# WAirU_v1_1.net
KiCad netlist of a schematic drawn in EAGLE
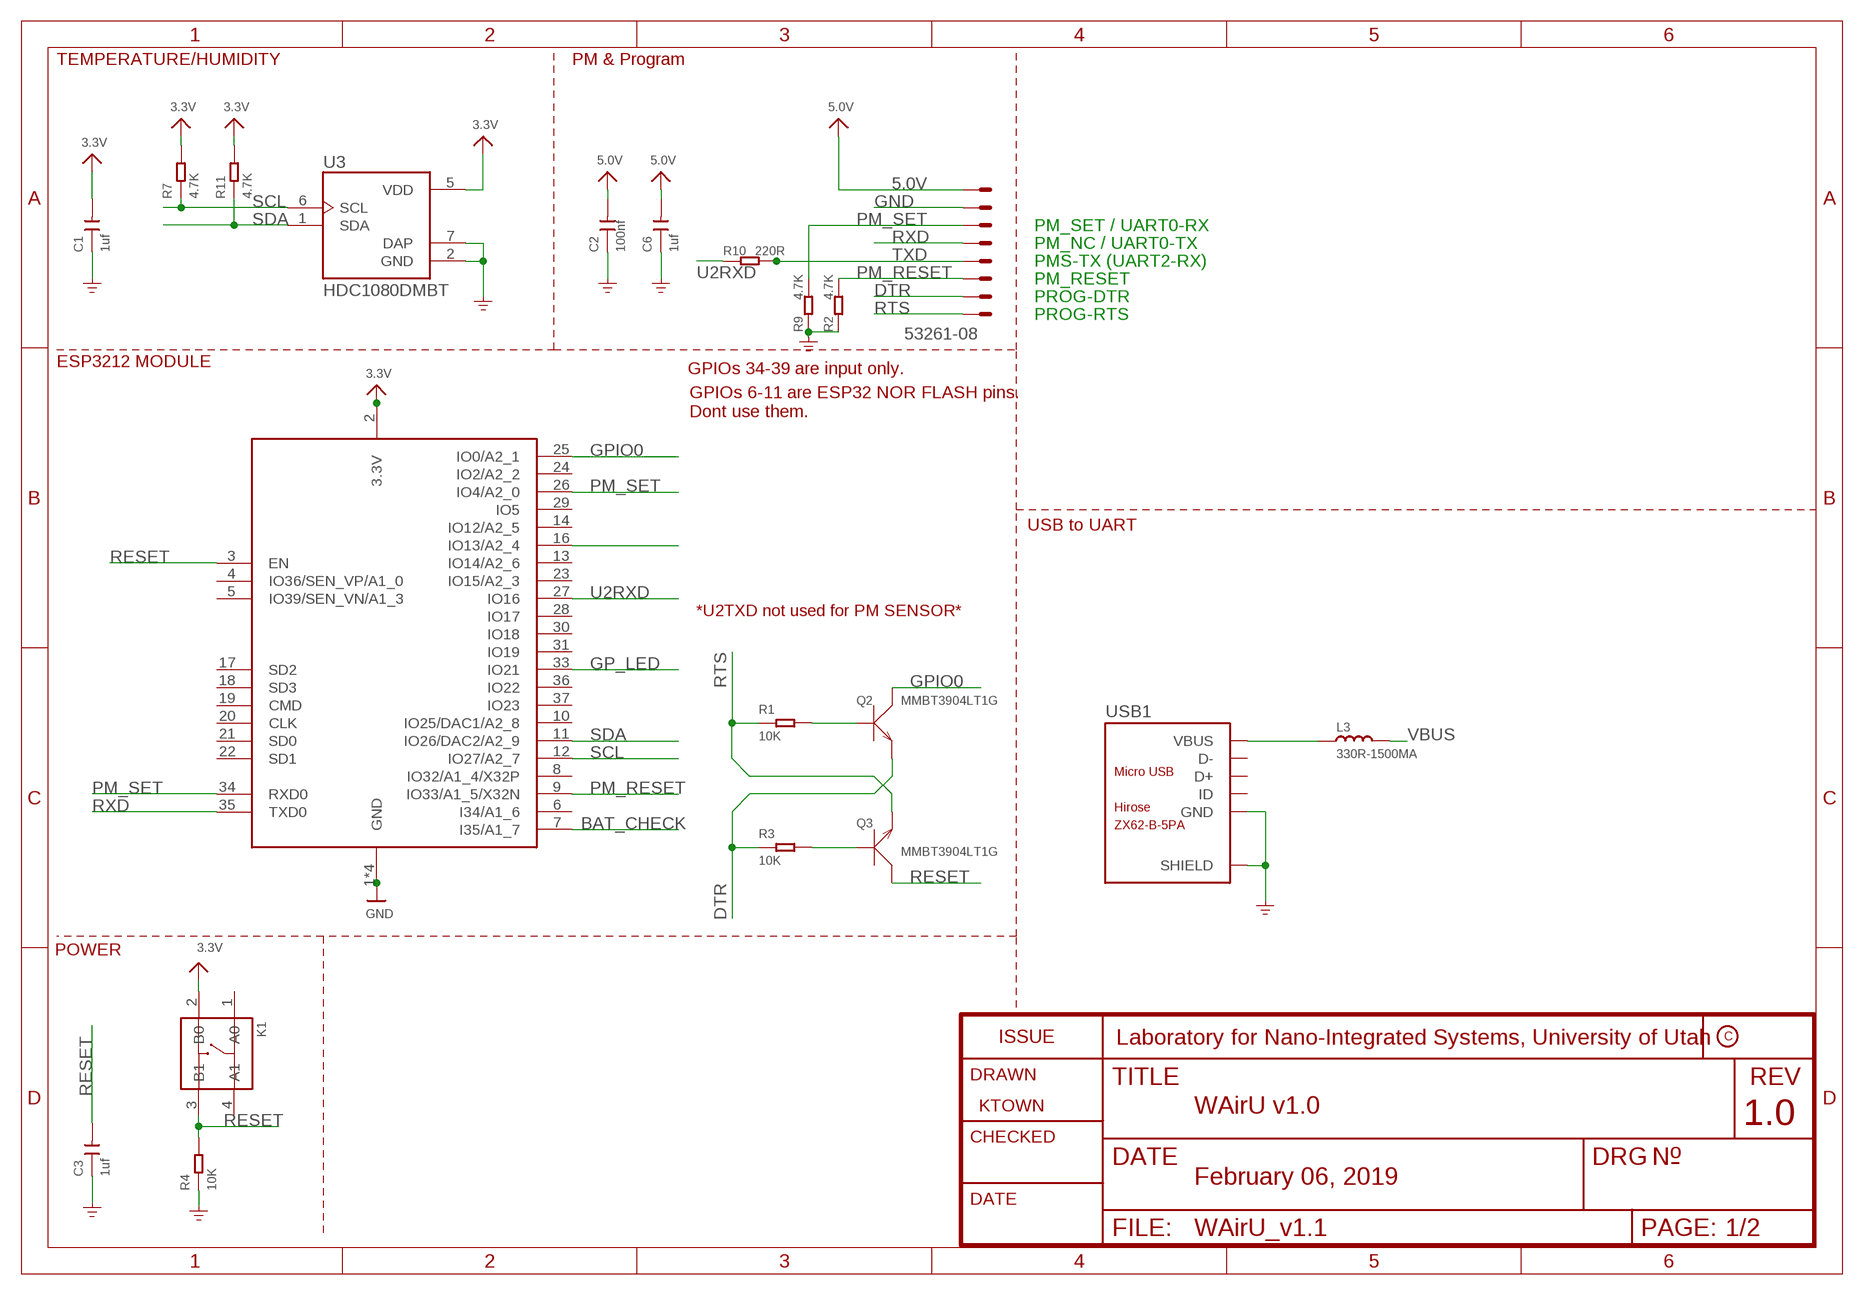
[diagram p0: schematic, sheet 1]
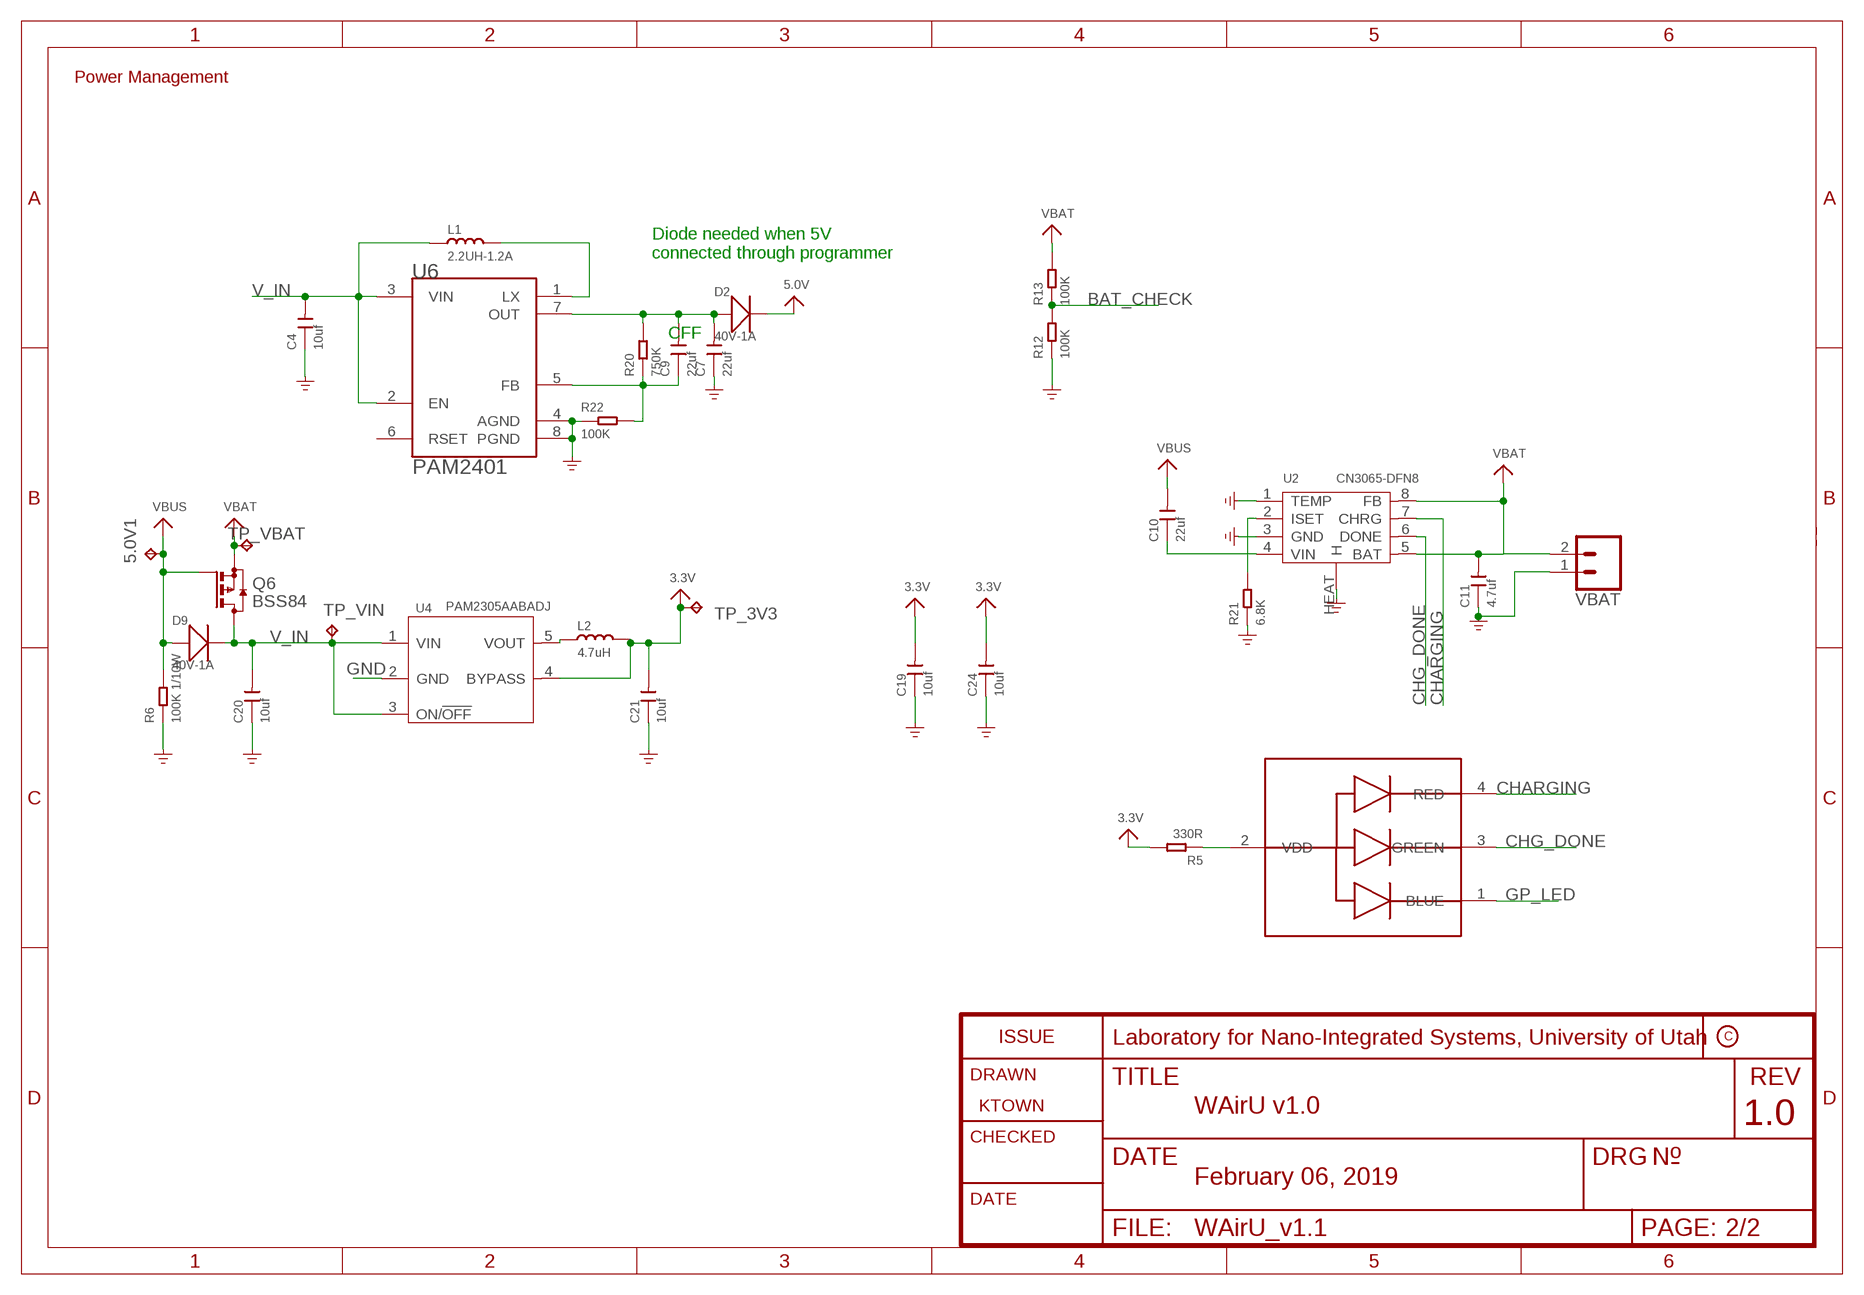
[diagram p1: schematic, sheet 2]

(export (version "E")
  (design (tool "Eeschema 10.0.6"))
  (components
    (comp (ref "5.0V1")
      (value "TPTP20SQ")
      (footprint "eagle-import:TP20SQ")
      (libsource (lib "eagle-import") (part "TPTP20SQ"))
    )
    (comp (ref "C4")
      (value "10uf")
      (footprint "eagle-import:C0603")
      (fields (field (name "MPN") "CC0603KRX5R6BB106"))
      (libsource (lib "eagle-import") (part "Seeed-Capacitor_CERAMIC-10UF-10V-10%-X5R(0603)"))
    )
    (comp (ref "C7")
      (value "22uf")
      (footprint "eagle-import:C0603")
      (fields (field (name "MPN") "CC0603KRX5R6BB106"))
      (libsource (lib "eagle-import") (part "CERAMIC-10UF-10V-10%-X5R(0603)"))
    )
    (comp (ref "C9")
      (value "22uf")
      (footprint "eagle-import:C0603")
      (fields (field (name "MPN") "CC0603KRX5R6BB106"))
      (libsource (lib "eagle-import") (part "CERAMIC-10UF-10V-10%-X5R(0603)"))
    )
    (comp (ref "C10")
      (value "22uf")
      (footprint "eagle-import:C0603")
      (fields (field (name "MPN") "CC0603KRX5R6BB106"))
      (libsource (lib "eagle-import") (part "CERAMIC-10UF-10V-10%-X5R(0603)"))
    )
    (comp (ref "C11")
      (value "4.7uf")
      (footprint "eagle-import:C0603")
      (fields (field (name "MPN") "CC0603KRX5R6BB475"))
      (libsource (lib "eagle-import") (part "CERAMIC-4.7UF-10V-10%-X5R(0603)"))
    )
    (comp (ref "C19")
      (value "10uf")
      (footprint "eagle-import:C0603")
      (fields (field (name "MPN") "CC0603KRX5R6BB106"))
      (libsource (lib "eagle-import") (part "Seeed-Capacitor_CERAMIC-10UF-10V-10%-X5R(0603)"))
    )
    (comp (ref "C20")
      (value "10uf")
      (footprint "eagle-import:C0603")
      (fields (field (name "MPN") "CC0603KRX5R6BB106"))
      (libsource (lib "eagle-import") (part "Seeed-Capacitor_CERAMIC-10UF-10V-10%-X5R(0603)"))
    )
    (comp (ref "C21")
      (value "10uf")
      (footprint "eagle-import:C0603")
      (fields (field (name "MPN") "CC0603KRX5R6BB106"))
      (libsource (lib "eagle-import") (part "Seeed-Capacitor_CERAMIC-10UF-10V-10%-X5R(0603)"))
    )
    (comp (ref "C24")
      (value "10uf")
      (footprint "eagle-import:C0603")
      (fields (field (name "MPN") "CC0603KRX5R6BB106"))
      (libsource (lib "eagle-import") (part "Seeed-Capacitor_CERAMIC-10UF-10V-10%-X5R(0603)"))
    )
    (comp (ref "D2")
      (value "40V-1A")
      (footprint "eagle-import:DO-214AC")
      (fields (field (name "MPN") "1N5819"))
      (libsource (lib "eagle-import") (part "SMD-DIODE-SCHOTTKY-40V-1A(DO-214AC)"))
    )
    (comp (ref "D9")
      (value "40V-1A")
      (footprint "eagle-import:DO-214AC")
      (fields (field (name "MPN") "1N5819"))
      (libsource (lib "eagle-import") (part "SMD-DIODE-SCHOTTKY-40V-1A(DO-214AC)"))
    )
    (comp (ref "L1")
      (value "2.2UH-1.2A")
      (footprint "eagle-import:L0805")
      (fields (field (name "MPN") "LQM2MPN2R2MG0"))
      (libsource (lib "eagle-import") (part "SMD-INDUCTOR-2.2UH-20%-1.2A(0805)"))
    )
    (comp (ref "L2")
      (value "4.7uH")
      (footprint "eagle-import:L5040S")
      (libsource (lib "eagle-import") (part "SMD-INDUCTOR-10UH-20%-2.35A(2P-5X5X4MM)"))
    )
    (comp (ref "Q6")
      (value "BSS84")
      (footprint "eagle-import:SOT23")
      (fields (field (name "MF") "MICROSS/On Semiconductor"))
      (libsource (lib "eagle-import") (part "BSS84"))
    )
    (comp (ref "R5")
      (value "330R")
      (footprint "eagle-import:R0603")
      (fields (field (name "MPN") "RC0603FR-07330RL"))
      (libsource (lib "eagle-import") (part "SMD-RES-330R-1%-1/10W(0603)"))
    )
    (comp (ref "R6")
      (value "100K 1/10W")
      (footprint "eagle-import:R0603")
      (fields (field (name "MPN") "RC0603JR-07100KL"))
      (libsource (lib "eagle-import") (part "Seeed-Resistor_SMD-RES-100K-5%-1/10W(0603)"))
    )
    (comp (ref "R12")
      (value "100K")
      (footprint "eagle-import:R0603")
      (fields (field (name "MPN") "RC0603JR-07100KL"))
      (libsource (lib "eagle-import") (part "SMD-RES-100K-5%-1/10W(0603)"))
    )
    (comp (ref "R13")
      (value "100K")
      (footprint "eagle-import:R0603")
      (fields (field (name "MPN") "RC0603JR-07100KL"))
      (libsource (lib "eagle-import") (part "SMD-RES-100K-5%-1/10W(0603)"))
    )
    (comp (ref "R20")
      (value "750K")
      (footprint "eagle-import:R0603")
      (fields (field (name "MPN") "RC0603JR-07100KL"))
      (libsource (lib "eagle-import") (part "SMD-RES-100K-5%-1/10W(0603)"))
    )
    (comp (ref "R21")
      (value "6.8K")
      (footprint "eagle-import:R0603")
      (fields (field (name "MPN") "RC0805JR-07220KL"))
      (libsource (lib "eagle-import") (part "SMD-RES-6.8K-1%-1/10W(0603)"))
    )
    (comp (ref "R22")
      (value "100K")
      (footprint "eagle-import:R0603")
      (fields (field (name "MPN") "RC0603JR-07100KL"))
      (libsource (lib "eagle-import") (part "SMD-RES-100K-5%-1/10W(0603)"))
    )
    (comp (ref "TP_3V3")
      (value "TPTP20SQ")
      (footprint "eagle-import:TP20SQ")
      (libsource (lib "eagle-import") (part "TPTP20SQ"))
    )
    (comp (ref "TP_VBAT")
      (value "TPTP20SQ")
      (footprint "eagle-import:TP20SQ")
      (libsource (lib "eagle-import") (part "TPTP20SQ"))
    )
    (comp (ref "TP_VIN")
      (value "TPTP20SQ")
      (footprint "eagle-import:TP20SQ")
      (libsource (lib "eagle-import") (part "TPTP20SQ"))
    )
    (comp (ref "U$4")
      (value "19-237A/BHR6GHC-M01/2T")
      (footprint "eagle-import:SMD-19-237A")
      (libsource (lib "eagle-import") (part "19-237A/BHR6GHC-M01/2T"))
    )
    (comp (ref "U2")
      (value "CN3065-DFN8")
      (footprint "eagle-import:DFN8G-0.5-3X3MM")
      (fields (field (name "MPN") "CN3065"))
      (libsource (lib "eagle-import") (part "PMIC-CN3065(DFN8)"))
    )
    (comp (ref "U4")
      (value "PAM2305AABADJ")
      (footprint "eagle-import:SOT-23-5")
      (fields (field (name "MPN") "LP2985-33DBVR"))
      (libsource (lib "eagle-import") (part "PMIC-LP2985-33DBVR(SOT23-5)"))
    )
    (comp (ref "U6")
      (value "PAM2401")
      (footprint "eagle-import:MSOP-8")
      (libsource (lib "eagle-import") (part "PAM2401"))
    )
    (comp (ref "VBAT")
      (value "CONN_02-JST-2MM-SMT")
      (footprint "eagle-import:JST-2-SMD")
      (libsource (lib "eagle-import") (part "CONN_02-JST-2MM-SMT"))
    )
    (comp (ref "C1")
      (value "1uf")
      (footprint "eagle-import:C0603")
      (fields (field (name "MPN") "CC0603KRX7R8BB105"))
      (libsource (lib "eagle-import") (part "CERAMIC-1UF-25V-10%-X7R(0603)"))
    )
    (comp (ref "C2")
      (value "100nf")
      (footprint "eagle-import:C0603")
      (fields (field (name "MPN") "CC0603KRX7R9BB104"))
      (libsource (lib "eagle-import") (part "CERAMIC-100NF-50V-10%-X7R(0603)"))
    )
    (comp (ref "C3")
      (value "1uf")
      (footprint "eagle-import:C0603")
      (fields (field (name "MPN") "CC0603KRX7R8BB105"))
      (libsource (lib "eagle-import") (part "CERAMIC-1UF-25V-10%-X7R(0603)"))
    )
    (comp (ref "C6")
      (value "1uf")
      (footprint "eagle-import:C0603")
      (fields (field (name "MPN") "CC0603KRX7R8BB105"))
      (libsource (lib "eagle-import") (part "CERAMIC-1UF-25V-10%-X7R(0603)"))
    )
    (comp (ref "K1")
      (value "SMD-SWITCH-TACTILE-SPST-NO(4P-D6.0MM)")
      (footprint "eagle-import:SW4-SMD-6.0X6.0X5.0MM")
      (fields (field (name "MPN") "DTSM-62K-S-V-T/R(SN431)"))
      (libsource (lib "eagle-import") (part "SMD-SWITCH-TACTILE-SPST-NO(4P-D6.0MM)"))
    )
    (comp (ref "L3")
      (value "330R-1500MA")
      (footprint "eagle-import:L0805")
      (fields (field (name "MPN") "BLM21PG331SN1D"))
      (libsource (lib "eagle-import") (part "SMD-FERRITE-BEAD-330R-1500MA(0805)'0805'"))
    )
    (comp (ref "MOLEX-53261-0871")
      (value "53261-08")
      (footprint "eagle-import:53261-08")
      (fields (field (name "MF") "MOLEX"))
      (libsource (lib "eagle-import") (part "53?-08261"))
    )
    (comp (ref "Q2")
      (value "MMBT3904LT1G")
      (footprint "eagle-import:SOT-23")
      (libsource (lib "eagle-import") (part "SMD-TRANSISTORS-NPN-40V-200MA-MMBT3904LT1G(SOT-23)"))
    )
    (comp (ref "Q3")
      (value "MMBT3904LT1G")
      (footprint "eagle-import:SOT-23")
      (libsource (lib "eagle-import") (part "SMD-TRANSISTORS-NPN-40V-200MA-MMBT3904LT1G(SOT-23)"))
    )
    (comp (ref "R1")
      (value "10K")
      (footprint "eagle-import:R0603")
      (fields (field (name "MPN") "RC0603FR-0710KL"))
      (libsource (lib "eagle-import") (part "SMD-RES-10K-1%-1/10W(0603)"))
    )
    (comp (ref "R2")
      (value "4.7K")
      (footprint "eagle-import:R0603")
      (fields (field (name "MPN") "RC0603JR-07220RL"))
      (libsource (lib "eagle-import") (part "SMD-RES-220R-5%-1/10W(0603)"))
    )
    (comp (ref "R3")
      (value "10K")
      (footprint "eagle-import:R0603")
      (fields (field (name "MPN") "RC0603FR-0710KL"))
      (libsource (lib "eagle-import") (part "SMD-RES-10K-1%-1/10W(0603)"))
    )
    (comp (ref "R4")
      (value "10K")
      (footprint "eagle-import:R0603")
      (fields (field (name "MPN") "RC0603FR-0710KL"))
      (libsource (lib "eagle-import") (part "SMD-RES-10K-1%-1/10W(0603)"))
    )
    (comp (ref "R7")
      (value "4.7K")
      (footprint "eagle-import:R0603")
      (fields (field (name "MPN") "RC0603JR-074K7L"))
      (libsource (lib "eagle-import") (part "SMD-RES-4.7K-5%-1/10W(0603)"))
    )
    (comp (ref "R9")
      (value "4.7K")
      (footprint "eagle-import:R0603")
      (fields (field (name "MPN") "RC0603JR-07220RL"))
      (libsource (lib "eagle-import") (part "SMD-RES-220R-5%-1/10W(0603)"))
    )
    (comp (ref "R10")
      (value "220R")
      (footprint "eagle-import:R0603")
      (fields (field (name "MPN") "RC0603JR-07220RL"))
      (libsource (lib "eagle-import") (part "SMD-RES-220R-5%-1/10W(0603)"))
    )
    (comp (ref "R11")
      (value "4.7K")
      (footprint "eagle-import:R0603")
      (fields (field (name "MPN") "RC0603JR-074K7L"))
      (libsource (lib "eagle-import") (part "SMD-RES-4.7K-5%-1/10W(0603)"))
    )
    (comp (ref "U3")
      (value "HDC1080DMBT")
      (footprint "eagle-import:SON100P300X300X80-7N")
      (fields (field (name "DIGI-KEY_PART_NUMBER") "296-43864-1-ND") (field (name "MF") "Texas Instruments"))
      (libsource (lib "eagle-import") (part "HDC1080DMBT"))
    )
    (comp (ref "U7")
      (value "ESP32_WROOM32_SKINNY")
      (footprint "eagle-import:WROOM32_SKINNY")
      (libsource (lib "eagle-import") (part "ESP32_WROOM32_SKINNY"))
    )
    (comp (ref "USB1")
      (value "ZX62-B-5PA")
      (footprint "eagle-import:MICRO-USB5+6P-SMD-0.65-AB")
      (libsource (lib "eagle-import") (part "MICRO-USB-SMD(ZX62-B-5PA)"))
    )
  )
  (nets
    (net (code "1") (name "3.3V") (class "Default")
      (node (ref "C1") (pin "2") (pinfunction "2_2") (pintype "passive"))
      (node (ref "C19") (pin "2") (pinfunction "2_2") (pintype "passive"))
      (node (ref "C21") (pin "2") (pinfunction "2_2") (pintype "passive"))
      (node (ref "C24") (pin "2") (pinfunction "2_2") (pintype "passive"))
      (node (ref "K1") (pin "2") (pinfunction "B0_2") (pintype "bidirectional"))
      (node (ref "L2") (pin "2") (pinfunction "2_2") (pintype "passive"))
      (node (ref "R11") (pin "2") (pinfunction "2_2") (pintype "passive"))
      (node (ref "R5") (pin "2") (pinfunction "2_2") (pintype "passive"))
      (node (ref "R7") (pin "2") (pinfunction "2_2") (pintype "passive"))
      (node (ref "TP_3V3") (pin "TP") (pinfunction "TP_TP") (pintype "input"))
      (node (ref "U3") (pin "5") (pinfunction "VDD_5") (pintype "power_in"))
      (node (ref "U4") (pin "4") (pinfunction "BYPASS_4") (pintype "bidirectional"))
      (node (ref "U7") (pin "2") (pinfunction "3.3V_2") (pintype "passive"))
    )
    (net (code "2") (name "5.0V") (class "Default")
      (node (ref "C2") (pin "2") (pinfunction "2_2") (pintype "passive"))
      (node (ref "C6") (pin "2") (pinfunction "2_2") (pintype "passive"))
      (node (ref "D2") (pin "2") (pinfunction "-_2") (pintype "passive"))
      (node (ref "MOLEX-53261-0871") (pin "8") (pinfunction "S_8") (pintype "passive"))
    )
    (net (code "3") (name "BAT_CHECK") (class "Default")
      (node (ref "R12") (pin "2") (pinfunction "2_2") (pintype "passive"))
      (node (ref "R13") (pin "1") (pinfunction "1_1") (pintype "passive"))
      (node (ref "U7") (pin "7") (pinfunction "I35/A1_7_7") (pintype "bidirectional"))
    )
    (net (code "4") (name "CHARGING") (class "Default")
      (node (ref "U$4") (pin "4") (pinfunction "RED_4") (pintype "bidirectional"))
      (node (ref "U2") (pin "7") (pinfunction "CHRG_7") (pintype "bidirectional"))
    )
    (net (code "5") (name "CHG_DONE") (class "Default")
      (node (ref "U$4") (pin "3") (pinfunction "GREEN_3") (pintype "bidirectional"))
      (node (ref "U2") (pin "6") (pinfunction "DONE_6") (pintype "bidirectional"))
    )
    (net (code "6") (name "DTR") (class "Default")
      (node (ref "MOLEX-53261-0871") (pin "2") (pinfunction "S_2") (pintype "passive"))
      (node (ref "Q2") (pin "2") (pinfunction "E_2") (pintype "passive"))
      (node (ref "R3") (pin "1") (pinfunction "1_1") (pintype "passive"))
    )
    (net (code "7") (name "GND") (class "Default")
      (node (ref "C1") (pin "1") (pinfunction "1_1") (pintype "passive"))
      (node (ref "C11") (pin "1") (pinfunction "1_1") (pintype "passive"))
      (node (ref "C19") (pin "1") (pinfunction "1_1") (pintype "passive"))
      (node (ref "C2") (pin "1") (pinfunction "1_1") (pintype "passive"))
      (node (ref "C20") (pin "1") (pinfunction "1_1") (pintype "passive"))
      (node (ref "C21") (pin "1") (pinfunction "1_1") (pintype "passive"))
      (node (ref "C24") (pin "1") (pinfunction "1_1") (pintype "passive"))
      (node (ref "C3") (pin "1") (pinfunction "1_1") (pintype "passive"))
      (node (ref "C4") (pin "1") (pinfunction "1_1") (pintype "passive"))
      (node (ref "C6") (pin "1") (pinfunction "1_1") (pintype "passive"))
      (node (ref "C7") (pin "1") (pinfunction "1_1") (pintype "passive"))
      (node (ref "MOLEX-53261-0871") (pin "7") (pinfunction "S_7") (pintype "passive"))
      (node (ref "R12") (pin "1") (pinfunction "1_1") (pintype "passive"))
      (node (ref "R2") (pin "1") (pinfunction "1_1") (pintype "passive"))
      (node (ref "R21") (pin "1") (pinfunction "1_1") (pintype "passive"))
      (node (ref "R22") (pin "1") (pinfunction "1_1") (pintype "passive"))
      (node (ref "R4") (pin "1") (pinfunction "1_1") (pintype "passive"))
      (node (ref "R6") (pin "1") (pinfunction "1_1") (pintype "passive"))
      (node (ref "R9") (pin "1") (pinfunction "1_1") (pintype "passive"))
      (node (ref "U2") (pin "1") (pinfunction "TEMP_1") (pintype "input"))
      (node (ref "U2") (pin "3") (pinfunction "GND_3") (pintype "power_in"))
      (node (ref "U2") (pin "HEAT") (pinfunction "H_HEAT") (pintype "bidirectional"))
      (node (ref "U3") (pin "2") (pinfunction "GND_2") (pintype "power_in"))
      (node (ref "U3") (pin "7") (pinfunction "DAP_7") (pintype "power_in"))
      (node (ref "U4") (pin "2") (pinfunction "GND_2") (pintype "bidirectional"))
      (node (ref "U6") (pin "4") (pinfunction "AGND_4") (pintype "bidirectional"))
      (node (ref "U6") (pin "8") (pinfunction "PGND_8") (pintype "bidirectional"))
      (node (ref "U7") (pin "1") (pinfunction "GND_1") (pintype "passive"))
      (node (ref "U7") (pin "15") (pinfunction "GND_15") (pintype "passive"))
      (node (ref "U7") (pin "38") (pinfunction "GND_38") (pintype "passive"))
      (node (ref "U7") (pin "P$1") (pinfunction "GND_P$1") (pintype "passive"))
      (node (ref "USB1") (pin "5") (pinfunction "GND_5") (pintype "power_in"))
      (node (ref "USB1") (pin "P1") (pinfunction "SHIELD_P1") (pintype "power_in"))
      (node (ref "USB1") (pin "P2") (pinfunction "SHIELD_P2") (pintype "power_in"))
      (node (ref "USB1") (pin "P3_1") (pinfunction "SHIELD_P3_1") (pintype "power_in"))
      (node (ref "USB1") (pin "P3_2") (pinfunction "SHIELD_P3_2") (pintype "power_in"))
      (node (ref "USB1") (pin "P3_3") (pinfunction "SHIELD_P3_3") (pintype "power_in"))
      (node (ref "USB1") (pin "P4_1") (pinfunction "SHIELD_P4_1") (pintype "power_in"))
      (node (ref "USB1") (pin "P4_2") (pinfunction "SHIELD_P4_2") (pintype "power_in"))
      (node (ref "USB1") (pin "P4_3") (pinfunction "SHIELD_P4_3") (pintype "power_in"))
      (node (ref "USB1") (pin "P5") (pinfunction "SHIELD_P5") (pintype "power_in"))
      (node (ref "USB1") (pin "P6") (pinfunction "SHIELD_P6") (pintype "power_in"))
      (node (ref "VBAT") (pin "1") (pinfunction "2_1") (pintype "passive"))
    )
    (net (code "8") (name "GPIO0") (class "Default")
      (node (ref "Q2") (pin "3") (pinfunction "C_3") (pintype "passive"))
      (node (ref "U7") (pin "25") (pinfunction "IO0/A2_1_25") (pintype "bidirectional"))
    )
    (net (code "9") (name "GP_LED") (class "Default")
      (node (ref "U$4") (pin "1") (pinfunction "BLUE_1") (pintype "bidirectional"))
      (node (ref "U7") (pin "33") (pinfunction "IO21_33") (pintype "bidirectional"))
    )
    (net (code "10") (name "Net-(D2-+)") (class "Default")
      (node (ref "C7") (pin "2") (pinfunction "2_2") (pintype "passive"))
      (node (ref "C9") (pin "2") (pinfunction "2_2") (pintype "passive"))
      (node (ref "D2") (pin "1") (pinfunction "+_1") (pintype "passive"))
      (node (ref "R20") (pin "2") (pinfunction "2_2") (pintype "passive"))
      (node (ref "U6") (pin "7") (pinfunction "OUT_7") (pintype "bidirectional"))
    )
    (net (code "11") (name "Net-(Q2-B)") (class "Default")
      (node (ref "Q2") (pin "1") (pinfunction "B_1") (pintype "passive"))
      (node (ref "R1") (pin "2") (pinfunction "2_2") (pintype "passive"))
    )
    (net (code "12") (name "Net-(Q3-B)") (class "Default")
      (node (ref "Q3") (pin "1") (pinfunction "B_1") (pintype "passive"))
      (node (ref "R3") (pin "2") (pinfunction "2_2") (pintype "passive"))
    )
    (net (code "13") (name "Net-(U$4-VDD)") (class "Default")
      (node (ref "R5") (pin "1") (pinfunction "1_1") (pintype "passive"))
      (node (ref "U$4") (pin "2") (pinfunction "VDD_2") (pintype "bidirectional"))
    )
    (net (code "14") (name "Net-(U2-ISET)") (class "Default")
      (node (ref "R21") (pin "2") (pinfunction "2_2") (pintype "passive"))
      (node (ref "U2") (pin "2") (pinfunction "ISET_2") (pintype "bidirectional"))
    )
    (net (code "15") (name "Net-(U2-VIN)") (class "Default")
      (node (ref "C10") (pin "1") (pinfunction "1_1") (pintype "passive"))
      (node (ref "U2") (pin "4") (pinfunction "VIN_4") (pintype "input"))
    )
    (net (code "16") (name "Net-(U4-VOUT)") (class "Default")
      (node (ref "L2") (pin "1") (pinfunction "1_1") (pintype "passive"))
      (node (ref "U4") (pin "5") (pinfunction "VOUT_5") (pintype "bidirectional"))
    )
    (net (code "17") (name "Net-(U6-FB)") (class "Default")
      (node (ref "C9") (pin "1") (pinfunction "1_1") (pintype "passive"))
      (node (ref "R20") (pin "1") (pinfunction "1_1") (pintype "passive"))
      (node (ref "R22") (pin "2") (pinfunction "2_2") (pintype "passive"))
      (node (ref "U6") (pin "5") (pinfunction "FB_5") (pintype "bidirectional"))
    )
    (net (code "18") (name "Net-(U6-LX)") (class "Default")
      (node (ref "L1") (pin "2") (pinfunction "2_2") (pintype "passive"))
      (node (ref "U6") (pin "1") (pinfunction "LX_1") (pintype "bidirectional"))
    )
    (net (code "19") (name "Net-(USB1-VBUS)") (class "Default")
      (node (ref "L3") (pin "1") (pinfunction "1_1") (pintype "passive"))
      (node (ref "USB1") (pin "1") (pinfunction "VBUS_1") (pintype "power_in"))
    )
    (net (code "20") (name "PM_RESET") (class "Default")
      (node (ref "MOLEX-53261-0871") (pin "3") (pinfunction "S_3") (pintype "passive"))
      (node (ref "R2") (pin "2") (pinfunction "2_2") (pintype "passive"))
      (node (ref "U7") (pin "9") (pinfunction "IO33/A1_5/X32N_9") (pintype "bidirectional"))
    )
    (net (code "21") (name "PM_SET") (class "Default")
      (node (ref "MOLEX-53261-0871") (pin "6") (pinfunction "S_6") (pintype "passive"))
      (node (ref "R9") (pin "2") (pinfunction "2_2") (pintype "passive"))
      (node (ref "U7") (pin "26") (pinfunction "IO4/A2_0_26") (pintype "bidirectional"))
      (node (ref "U7") (pin "34") (pinfunction "RXD0_34") (pintype "input"))
    )
    (net (code "22") (name "RESET") (class "Default")
      (node (ref "C3") (pin "2") (pinfunction "2_2") (pintype "passive"))
      (node (ref "K1") (pin "3") (pinfunction "B1_3") (pintype "bidirectional"))
      (node (ref "Q3") (pin "3") (pinfunction "C_3") (pintype "passive"))
      (node (ref "R4") (pin "2") (pinfunction "2_2") (pintype "passive"))
      (node (ref "U7") (pin "3") (pinfunction "EN_3") (pintype "input"))
    )
    (net (code "23") (name "RTS") (class "Default")
      (node (ref "MOLEX-53261-0871") (pin "1") (pinfunction "S_1") (pintype "passive"))
      (node (ref "Q3") (pin "2") (pinfunction "E_2") (pintype "passive"))
      (node (ref "R1") (pin "1") (pinfunction "1_1") (pintype "passive"))
    )
    (net (code "24") (name "RXD") (class "Default")
      (node (ref "MOLEX-53261-0871") (pin "5") (pinfunction "S_5") (pintype "passive"))
      (node (ref "U7") (pin "35") (pinfunction "TXD0_35") (pintype "output"))
    )
    (net (code "25") (name "SCL") (class "Default")
      (node (ref "R7") (pin "1") (pinfunction "1_1") (pintype "passive"))
      (node (ref "U3") (pin "6") (pinfunction "SCL_6") (pintype "input"))
      (node (ref "U7") (pin "12") (pinfunction "IO27/A2_7_12") (pintype "bidirectional"))
    )
    (net (code "26") (name "SDA") (class "Default")
      (node (ref "R11") (pin "1") (pinfunction "1_1") (pintype "passive"))
      (node (ref "U3") (pin "1") (pinfunction "SDA_1") (pintype "bidirectional"))
      (node (ref "U7") (pin "11") (pinfunction "IO26/DAC2/A2_9_11") (pintype "bidirectional"))
    )
    (net (code "27") (name "TXD") (class "Default")
      (node (ref "MOLEX-53261-0871") (pin "4") (pinfunction "S_4") (pintype "passive"))
      (node (ref "R10") (pin "2") (pinfunction "2_2") (pintype "passive"))
    )
    (net (code "28") (name "U2RXD") (class "Default")
      (node (ref "R10") (pin "1") (pinfunction "1_1") (pintype "passive"))
      (node (ref "U7") (pin "27") (pinfunction "IO16_27") (pintype "bidirectional"))
    )
    (net (code "29") (name "VBAT") (class "Default")
      (node (ref "C11") (pin "2") (pinfunction "2_2") (pintype "passive"))
      (node (ref "Q6") (pin "2") (pinfunction "S_2") (pintype "passive"))
      (node (ref "R13") (pin "2") (pinfunction "2_2") (pintype "passive"))
      (node (ref "TP_VBAT") (pin "TP") (pinfunction "TP_TP") (pintype "input"))
      (node (ref "U2") (pin "5") (pinfunction "BAT_5") (pintype "bidirectional"))
      (node (ref "U2") (pin "8") (pinfunction "FB_8") (pintype "input"))
      (node (ref "VBAT") (pin "2") (pinfunction "1_2") (pintype "passive"))
    )
    (net (code "30") (name "VBUS") (class "Default")
      (node (ref "5.0V1") (pin "TP") (pinfunction "TP_TP") (pintype "input"))
      (node (ref "C10") (pin "2") (pinfunction "2_2") (pintype "passive"))
      (node (ref "D9") (pin "1") (pinfunction "+_1") (pintype "passive"))
      (node (ref "L3") (pin "2") (pinfunction "2_2") (pintype "passive"))
      (node (ref "Q6") (pin "1") (pinfunction "G_1") (pintype "passive"))
      (node (ref "R6") (pin "2") (pinfunction "2_2") (pintype "passive"))
    )
    (net (code "31") (name "V_IN") (class "Default")
      (node (ref "C20") (pin "2") (pinfunction "2_2") (pintype "passive"))
      (node (ref "C4") (pin "2") (pinfunction "2_2") (pintype "passive"))
      (node (ref "D9") (pin "2") (pinfunction "-_2") (pintype "passive"))
      (node (ref "L1") (pin "1") (pinfunction "1_1") (pintype "passive"))
      (node (ref "Q6") (pin "3") (pinfunction "D_3") (pintype "passive"))
      (node (ref "TP_VIN") (pin "TP") (pinfunction "TP_TP") (pintype "input"))
      (node (ref "U4") (pin "1") (pinfunction "VIN_1") (pintype "bidirectional"))
      (node (ref "U4") (pin "3") (pinfunction "ON/~{OFF}_3") (pintype "bidirectional"))
      (node (ref "U6") (pin "2") (pinfunction "EN_2") (pintype "bidirectional"))
      (node (ref "U6") (pin "3") (pinfunction "VIN_3") (pintype "bidirectional"))
    )
    (net (code "32") (name "unconnected-(K1-A0-Pad1)") (class "Default")
      (node (ref "K1") (pin "1") (pinfunction "A0_1") (pintype "bidirectional"))
    )
    (net (code "33") (name "unconnected-(K1-A1-Pad4)") (class "Default")
      (node (ref "K1") (pin "4") (pinfunction "A1_4") (pintype "bidirectional"))
    )
    (net (code "34") (name "unconnected-(U6-RSET-Pad6)") (class "Default")
      (node (ref "U6") (pin "6") (pinfunction "RSET_6") (pintype "bidirectional"))
    )
    (net (code "35") (name "unconnected-(U7-CLK-Pad20)") (class "Default")
      (node (ref "U7") (pin "20") (pinfunction "CLK_20") (pintype "bidirectional"))
    )
    (net (code "36") (name "unconnected-(U7-CMD-Pad19)") (class "Default")
      (node (ref "U7") (pin "19") (pinfunction "CMD_19") (pintype "bidirectional"))
    )
    (net (code "37") (name "unconnected-(U7-I34{slash}A1_6-Pad6)") (class "Default")
      (node (ref "U7") (pin "6") (pinfunction "I34/A1_6_6") (pintype "bidirectional"))
    )
    (net (code "38") (name "unconnected-(U7-IO2{slash}A2_2-Pad24)") (class "Default")
      (node (ref "U7") (pin "24") (pinfunction "IO2/A2_2_24") (pintype "bidirectional"))
    )
    (net (code "39") (name "unconnected-(U7-IO5-Pad29)") (class "Default")
      (node (ref "U7") (pin "29") (pinfunction "IO5_29") (pintype "bidirectional"))
    )
    (net (code "40") (name "unconnected-(U7-IO12{slash}A2_5-Pad14)") (class "Default")
      (node (ref "U7") (pin "14") (pinfunction "IO12/A2_5_14") (pintype "bidirectional"))
    )
    (net (code "41") (name "unconnected-(U7-IO13{slash}A2_4-Pad16)") (class "Default")
      (node (ref "U7") (pin "16") (pinfunction "IO13/A2_4_16") (pintype "bidirectional"))
    )
    (net (code "42") (name "unconnected-(U7-IO14{slash}A2_6-Pad13)") (class "Default")
      (node (ref "U7") (pin "13") (pinfunction "IO14/A2_6_13") (pintype "bidirectional"))
    )
    (net (code "43") (name "unconnected-(U7-IO15{slash}A2_3-Pad23)") (class "Default")
      (node (ref "U7") (pin "23") (pinfunction "IO15/A2_3_23") (pintype "bidirectional"))
    )
    (net (code "44") (name "unconnected-(U7-IO17-Pad28)") (class "Default")
      (node (ref "U7") (pin "28") (pinfunction "IO17_28") (pintype "bidirectional"))
    )
    (net (code "45") (name "unconnected-(U7-IO18-Pad30)") (class "Default")
      (node (ref "U7") (pin "30") (pinfunction "IO18_30") (pintype "bidirectional"))
    )
    (net (code "46") (name "unconnected-(U7-IO19-Pad31)") (class "Default")
      (node (ref "U7") (pin "31") (pinfunction "IO19_31") (pintype "bidirectional"))
    )
    (net (code "47") (name "unconnected-(U7-IO22-Pad36)") (class "Default")
      (node (ref "U7") (pin "36") (pinfunction "IO22_36") (pintype "bidirectional"))
    )
    (net (code "48") (name "unconnected-(U7-IO23-Pad37)") (class "Default")
      (node (ref "U7") (pin "37") (pinfunction "IO23_37") (pintype "bidirectional"))
    )
    (net (code "49") (name "unconnected-(U7-IO25{slash}DAC1{slash}A2_8-Pad10)") (class "Default")
      (node (ref "U7") (pin "10") (pinfunction "IO25/DAC1/A2_8_10") (pintype "bidirectional"))
    )
    (net (code "50") (name "unconnected-(U7-IO32{slash}A1_4{slash}X32P-Pad8)") (class "Default")
      (node (ref "U7") (pin "8") (pinfunction "IO32/A1_4/X32P_8") (pintype "bidirectional"))
    )
    (net (code "51") (name "unconnected-(U7-IO36{slash}SEN_VP{slash}A1_0-Pad4)") (class "Default")
      (node (ref "U7") (pin "4") (pinfunction "IO36/SEN_VP/A1_0_4") (pintype "passive"))
    )
    (net (code "52") (name "unconnected-(U7-IO39{slash}SEN_VN{slash}A1_3-Pad5)") (class "Default")
      (node (ref "U7") (pin "5") (pinfunction "IO39/SEN_VN/A1_3_5") (pintype "passive"))
    )
    (net (code "53") (name "unconnected-(U7-SD0-Pad21)") (class "Default")
      (node (ref "U7") (pin "21") (pinfunction "SD0_21") (pintype "bidirectional"))
    )
    (net (code "54") (name "unconnected-(U7-SD1-Pad22)") (class "Default")
      (node (ref "U7") (pin "22") (pinfunction "SD1_22") (pintype "bidirectional"))
    )
    (net (code "55") (name "unconnected-(U7-SD2-Pad17)") (class "Default")
      (node (ref "U7") (pin "17") (pinfunction "SD2_17") (pintype "bidirectional"))
    )
    (net (code "56") (name "unconnected-(U7-SD3-Pad18)") (class "Default")
      (node (ref "U7") (pin "18") (pinfunction "SD3_18") (pintype "bidirectional"))
    )
    (net (code "57") (name "unconnected-(USB1-D+-Pad3)") (class "Default")
      (node (ref "USB1") (pin "3") (pinfunction "D+_3") (pintype "bidirectional"))
    )
    (net (code "58") (name "unconnected-(USB1-D--Pad2)") (class "Default")
      (node (ref "USB1") (pin "2") (pinfunction "D-_2") (pintype "bidirectional"))
    )
    (net (code "59") (name "unconnected-(USB1-ID-Pad4)") (class "Default")
      (node (ref "USB1") (pin "4") (pinfunction "ID_4") (pintype "bidirectional"))
    )
  )
)
